# HC-SR04-SCANNER-v1-1.net
KiCad netlist of a schematic drawn in EAGLE
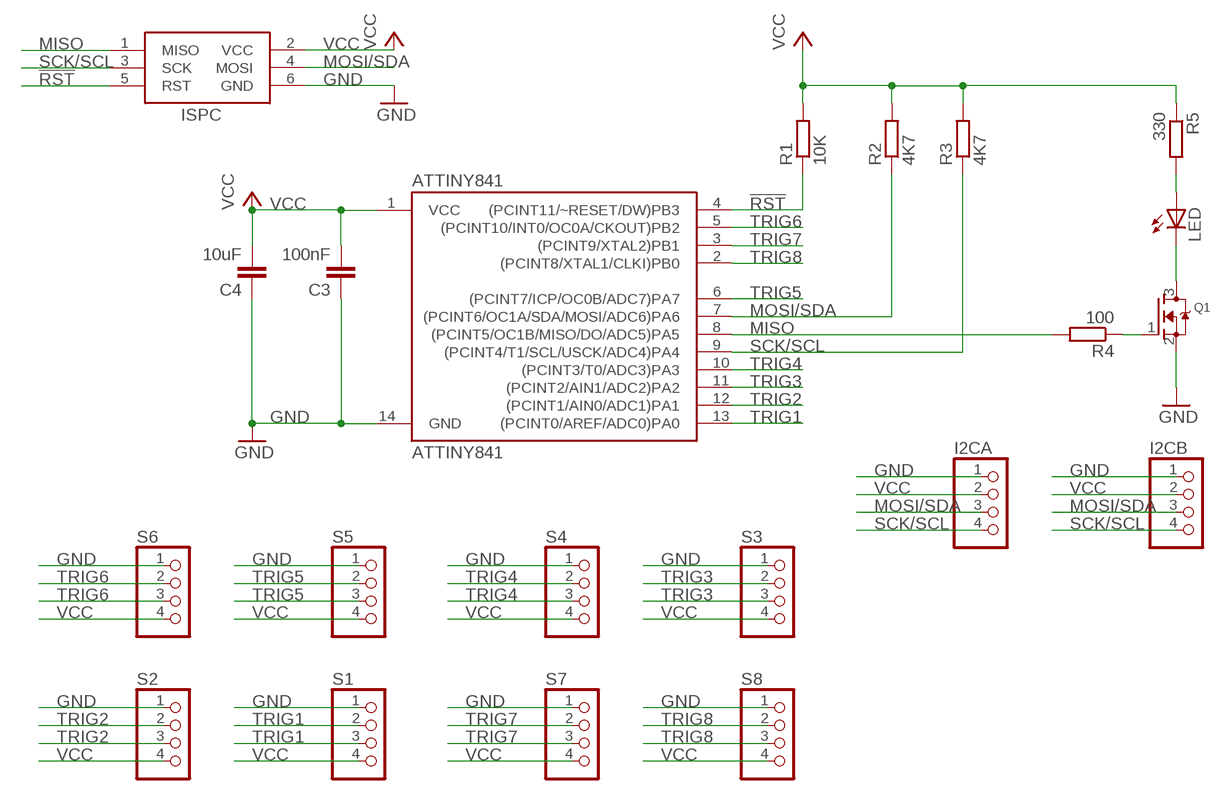
[diagram p0: schematic, sheet 1]

(export (version "E")
  (design (tool "Eeschema 10.0.6"))
  (components
    (comp (ref "ATTINY841")
      (value "ATTINY841")
      (footprint "eagle-import:SO14")
      (libsource (lib "eagle-import") (part "ATTINY84"))
    )
    (comp (ref "C3")
      (value "100nF")
      (footprint "eagle-import:C0805K")
      (libsource (lib "eagle-import") (part "C-EUC0805K"))
    )
    (comp (ref "C4")
      (value "10uF")
      (footprint "eagle-import:C0805K")
      (libsource (lib "eagle-import") (part "C-EUC0805K"))
    )
    (comp (ref "I2CA")
      (value "PINHD-1X4")
      (footprint "eagle-import:1X04")
      (libsource (lib "eagle-import") (part "PINHD-1X4"))
    )
    (comp (ref "I2CB")
      (value "PINHD-1X4")
      (footprint "eagle-import:1X04")
      (libsource (lib "eagle-import") (part "PINHD-1X4"))
    )
    (comp (ref "ISPC")
      (value "AVRISP-6")
      (footprint "eagle-import:AVRISP")
      (libsource (lib "eagle-import") (part "AVRISP-6"))
    )
    (comp (ref "LED")
      (value "LED")
      (footprint "eagle-import:LED_0805")
      (libsource (lib "eagle-import") (part "LED"))
    )
    (comp (ref "Q1")
      (value "MOSFET-NREFLOW")
      (footprint "eagle-import:SOT23")
      (libsource (lib "eagle-import") (part "MOSFET-NREFLOW"))
    )
    (comp (ref "R1")
      (value "10K")
      (footprint "eagle-import:R0805")
      (libsource (lib "eagle-import") (part "R-EU_R0805"))
    )
    (comp (ref "R2")
      (value "4K7")
      (footprint "eagle-import:R0805")
      (libsource (lib "eagle-import") (part "R-EU_R0805"))
    )
    (comp (ref "R3")
      (value "4K7")
      (footprint "eagle-import:R0805")
      (libsource (lib "eagle-import") (part "R-EU_R0805"))
    )
    (comp (ref "R4")
      (value "100")
      (footprint "eagle-import:R0805")
      (libsource (lib "eagle-import") (part "R-EU_R0805"))
    )
    (comp (ref "R5")
      (value "330")
      (footprint "eagle-import:R0805")
      (libsource (lib "eagle-import") (part "R-EU_R0805"))
    )
    (comp (ref "S1")
      (value "PINHD-1X4")
      (footprint "eagle-import:1X04")
      (libsource (lib "eagle-import") (part "PINHD-1X4"))
    )
    (comp (ref "S2")
      (value "PINHD-1X4")
      (footprint "eagle-import:1X04")
      (libsource (lib "eagle-import") (part "PINHD-1X4"))
    )
    (comp (ref "S3")
      (value "PINHD-1X4")
      (footprint "eagle-import:1X04")
      (libsource (lib "eagle-import") (part "PINHD-1X4"))
    )
    (comp (ref "S4")
      (value "PINHD-1X4")
      (footprint "eagle-import:1X04")
      (libsource (lib "eagle-import") (part "PINHD-1X4"))
    )
    (comp (ref "S5")
      (value "PINHD-1X4")
      (footprint "eagle-import:1X04")
      (libsource (lib "eagle-import") (part "PINHD-1X4"))
    )
    (comp (ref "S6")
      (value "PINHD-1X4")
      (footprint "eagle-import:1X04")
      (libsource (lib "eagle-import") (part "PINHD-1X4"))
    )
    (comp (ref "S7")
      (value "PINHD-1X4")
      (footprint "eagle-import:1X04")
      (libsource (lib "eagle-import") (part "PINHD-1X4"))
    )
    (comp (ref "S8")
      (value "PINHD-1X4")
      (footprint "eagle-import:1X04")
      (libsource (lib "eagle-import") (part "PINHD-1X4"))
    )
  )
  (nets
    (net (code "1") (name "/MISO") (class "Default")
      (node (ref "ATTINY841") (pin "8") (pinfunction "(PCINT5/OC1B/MISO/DO/ADC5)PA5_8") (pintype "bidirectional"))
      (node (ref "ISPC") (pin "1") (pinfunction "MISO_1") (pintype "input"))
      (node (ref "R4") (pin "2") (pinfunction "2_2") (pintype "passive"))
    )
    (net (code "2") (name "/MOSI{slash}SDA") (class "Default")
      (node (ref "ATTINY841") (pin "7") (pinfunction "(PCINT6/OC1A/SDA/MOSI/ADC6)PA6_7") (pintype "bidirectional"))
      (node (ref "I2CA") (pin "3") (pinfunction "3_3") (pintype "passive"))
      (node (ref "I2CB") (pin "3") (pinfunction "3_3") (pintype "passive"))
      (node (ref "ISPC") (pin "4") (pinfunction "MOSI_4") (pintype "output"))
      (node (ref "R2") (pin "1") (pinfunction "1_1") (pintype "passive"))
    )
    (net (code "3") (name "/SCK{slash}SCL") (class "Default")
      (node (ref "ATTINY841") (pin "9") (pinfunction "(PCINT4/T1/SCL/USCK/ADC4)PA4_9") (pintype "bidirectional"))
      (node (ref "I2CA") (pin "4") (pinfunction "4_4") (pintype "passive"))
      (node (ref "I2CB") (pin "4") (pinfunction "4_4") (pintype "passive"))
      (node (ref "ISPC") (pin "3") (pinfunction "SCK_3") (pintype "output"))
      (node (ref "R3") (pin "1") (pinfunction "1_1") (pintype "passive"))
    )
    (net (code "4") (name "/TRIG1") (class "Default")
      (node (ref "ATTINY841") (pin "13") (pinfunction "(PCINT0/AREF/ADC0)PA0_13") (pintype "bidirectional"))
      (node (ref "S1") (pin "2") (pinfunction "2_2") (pintype "passive"))
      (node (ref "S1") (pin "3") (pinfunction "3_3") (pintype "passive"))
    )
    (net (code "5") (name "/TRIG2") (class "Default")
      (node (ref "ATTINY841") (pin "12") (pinfunction "(PCINT1/AIN0/ADC1)PA1_12") (pintype "bidirectional"))
      (node (ref "S2") (pin "2") (pinfunction "2_2") (pintype "passive"))
      (node (ref "S2") (pin "3") (pinfunction "3_3") (pintype "passive"))
    )
    (net (code "6") (name "/TRIG3") (class "Default")
      (node (ref "ATTINY841") (pin "11") (pinfunction "(PCINT2/AIN1/ADC2)PA2_11") (pintype "bidirectional"))
      (node (ref "S3") (pin "2") (pinfunction "2_2") (pintype "passive"))
      (node (ref "S3") (pin "3") (pinfunction "3_3") (pintype "passive"))
    )
    (net (code "7") (name "/TRIG4") (class "Default")
      (node (ref "ATTINY841") (pin "10") (pinfunction "(PCINT3/T0/ADC3)PA3_10") (pintype "bidirectional"))
      (node (ref "S4") (pin "2") (pinfunction "2_2") (pintype "passive"))
      (node (ref "S4") (pin "3") (pinfunction "3_3") (pintype "passive"))
    )
    (net (code "8") (name "/TRIG5") (class "Default")
      (node (ref "ATTINY841") (pin "6") (pinfunction "(PCINT7/ICP/OC0B/ADC7)PA7_6") (pintype "bidirectional"))
      (node (ref "S5") (pin "2") (pinfunction "2_2") (pintype "passive"))
      (node (ref "S5") (pin "3") (pinfunction "3_3") (pintype "passive"))
    )
    (net (code "9") (name "/TRIG6") (class "Default")
      (node (ref "ATTINY841") (pin "5") (pinfunction "(PCINT10/INT0/OC0A/CKOUT)PB2_5") (pintype "bidirectional"))
      (node (ref "S6") (pin "2") (pinfunction "2_2") (pintype "passive"))
      (node (ref "S6") (pin "3") (pinfunction "3_3") (pintype "passive"))
    )
    (net (code "10") (name "/TRIG7") (class "Default")
      (node (ref "ATTINY841") (pin "3") (pinfunction "(PCINT9/XTAL2)PB1_3") (pintype "bidirectional"))
      (node (ref "S7") (pin "2") (pinfunction "2_2") (pintype "passive"))
      (node (ref "S7") (pin "3") (pinfunction "3_3") (pintype "passive"))
    )
    (net (code "11") (name "/TRIG8") (class "Default")
      (node (ref "ATTINY841") (pin "2") (pinfunction "(PCINT8/XTAL1/CLKI)PB0_2") (pintype "bidirectional"))
      (node (ref "S8") (pin "2") (pinfunction "2_2") (pintype "passive"))
      (node (ref "S8") (pin "3") (pinfunction "3_3") (pintype "passive"))
    )
    (net (code "12") (name "/~{RST}") (class "Default")
      (node (ref "ATTINY841") (pin "4") (pinfunction "(PCINT11/~{RESET/DW})PB3_4") (pintype "bidirectional"))
      (node (ref "ISPC") (pin "5") (pinfunction "RST_5") (pintype "output"))
      (node (ref "R1") (pin "1") (pinfunction "1_1") (pintype "passive"))
    )
    (net (code "13") (name "GND") (class "Default")
      (node (ref "ATTINY841") (pin "14") (pinfunction "GND_14") (pintype "bidirectional"))
      (node (ref "C3") (pin "1") (pinfunction "1_1") (pintype "passive"))
      (node (ref "C4") (pin "1") (pinfunction "1_1") (pintype "passive"))
      (node (ref "I2CA") (pin "1") (pinfunction "1_1") (pintype "passive"))
      (node (ref "I2CB") (pin "1") (pinfunction "1_1") (pintype "passive"))
      (node (ref "ISPC") (pin "6") (pinfunction "GND_6") (pintype "power_in"))
      (node (ref "Q1") (pin "2") (pinfunction "S_2") (pintype "bidirectional"))
      (node (ref "S1") (pin "1") (pinfunction "1_1") (pintype "passive"))
      (node (ref "S2") (pin "1") (pinfunction "1_1") (pintype "passive"))
      (node (ref "S3") (pin "1") (pinfunction "1_1") (pintype "passive"))
      (node (ref "S4") (pin "1") (pinfunction "1_1") (pintype "passive"))
      (node (ref "S5") (pin "1") (pinfunction "1_1") (pintype "passive"))
      (node (ref "S6") (pin "1") (pinfunction "1_1") (pintype "passive"))
      (node (ref "S7") (pin "1") (pinfunction "1_1") (pintype "passive"))
      (node (ref "S8") (pin "1") (pinfunction "1_1") (pintype "passive"))
    )
    (net (code "14") (name "Net-(LED-A)") (class "Default")
      (node (ref "LED") (pin "1") (pinfunction "A_1") (pintype "passive"))
      (node (ref "R5") (pin "2") (pinfunction "2_2") (pintype "passive"))
    )
    (net (code "15") (name "Net-(LED-C)") (class "Default")
      (node (ref "LED") (pin "2") (pinfunction "C_2") (pintype "passive"))
      (node (ref "Q1") (pin "3") (pinfunction "D_3") (pintype "bidirectional"))
    )
    (net (code "16") (name "Net-(Q1-G)") (class "Default")
      (node (ref "Q1") (pin "1") (pinfunction "G_1") (pintype "bidirectional"))
      (node (ref "R4") (pin "1") (pinfunction "1_1") (pintype "passive"))
    )
    (net (code "17") (name "VCC") (class "Default")
      (node (ref "ATTINY841") (pin "1") (pinfunction "VCC_1") (pintype "bidirectional"))
      (node (ref "C3") (pin "2") (pinfunction "2_2") (pintype "passive"))
      (node (ref "C4") (pin "2") (pinfunction "2_2") (pintype "passive"))
      (node (ref "I2CA") (pin "2") (pinfunction "2_2") (pintype "passive"))
      (node (ref "I2CB") (pin "2") (pinfunction "2_2") (pintype "passive"))
      (node (ref "ISPC") (pin "2") (pinfunction "VCC_2") (pintype "power_in"))
      (node (ref "R1") (pin "2") (pinfunction "2_2") (pintype "passive"))
      (node (ref "R2") (pin "2") (pinfunction "2_2") (pintype "passive"))
      (node (ref "R3") (pin "2") (pinfunction "2_2") (pintype "passive"))
      (node (ref "R5") (pin "1") (pinfunction "1_1") (pintype "passive"))
      (node (ref "S1") (pin "4") (pinfunction "4_4") (pintype "passive"))
      (node (ref "S2") (pin "4") (pinfunction "4_4") (pintype "passive"))
      (node (ref "S3") (pin "4") (pinfunction "4_4") (pintype "passive"))
      (node (ref "S4") (pin "4") (pinfunction "4_4") (pintype "passive"))
      (node (ref "S5") (pin "4") (pinfunction "4_4") (pintype "passive"))
      (node (ref "S6") (pin "4") (pinfunction "4_4") (pintype "passive"))
      (node (ref "S7") (pin "4") (pinfunction "4_4") (pintype "passive"))
      (node (ref "S8") (pin "4") (pinfunction "4_4") (pintype "passive"))
    )
  )
)
